# LED_Matrix_MCI_Vorlage.net
KiCad netlist of a schematic drawn in Altium Designer
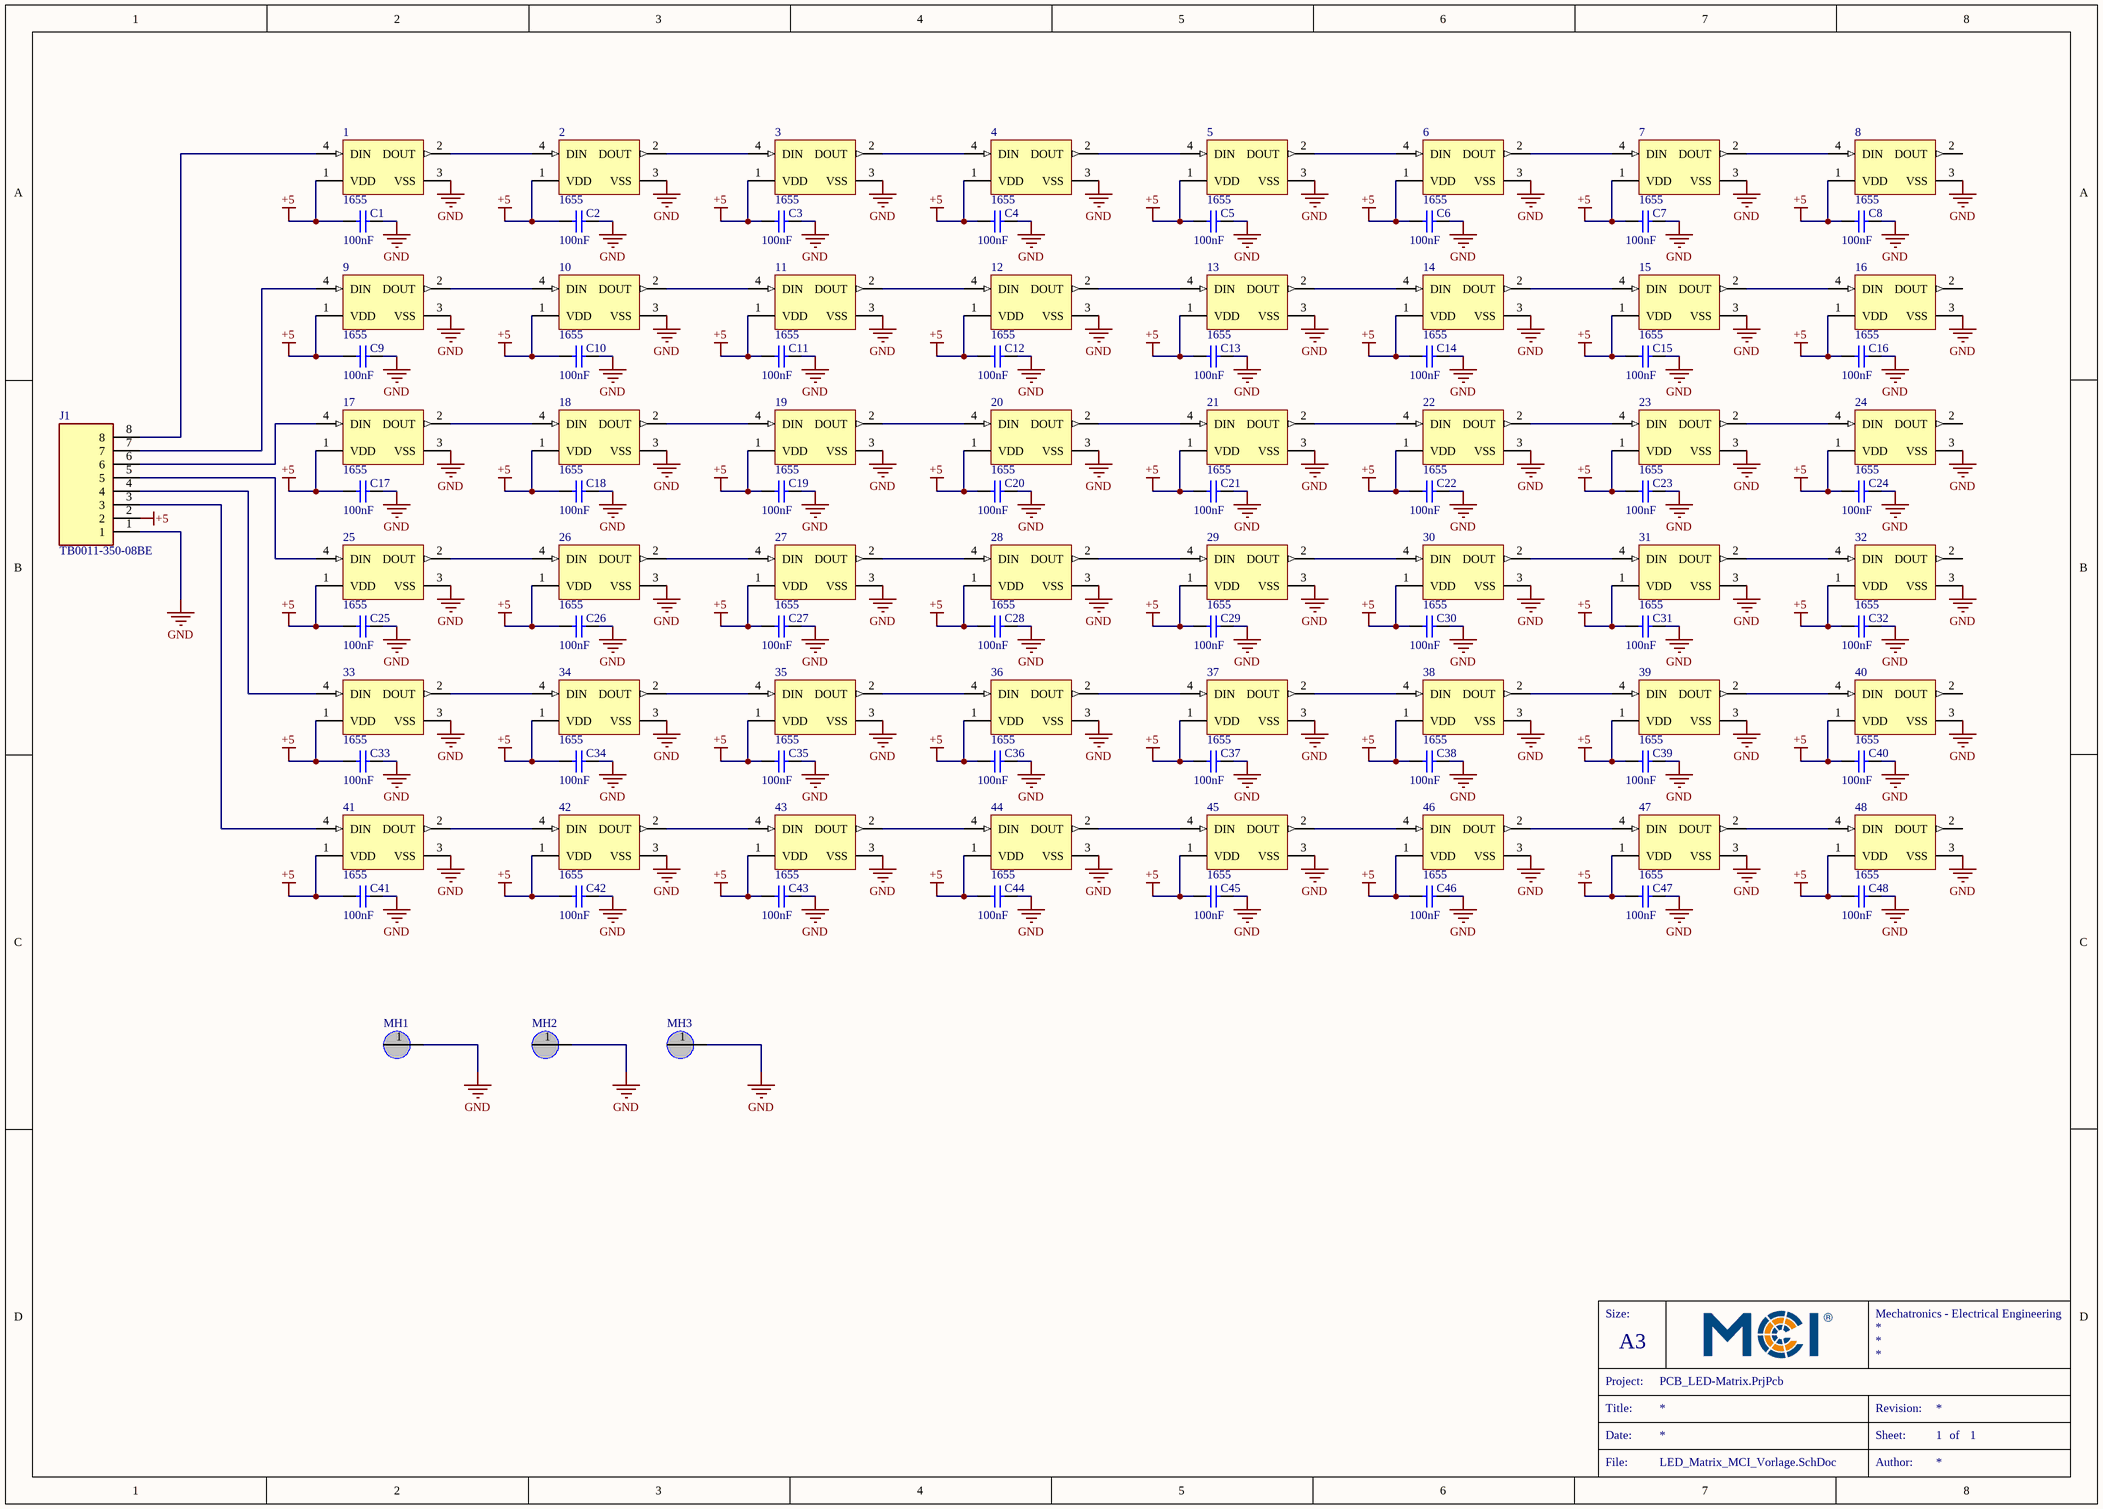
[diagram p0: LED_Matrix_MCI_Vorlage.SchDoc]

(export (version "E")
  (design (tool "Eeschema 10.0.6"))
  (components
    (comp (ref "1")
      (value "1655")
      (footprint "ADA-RGB-1655_V")
      (fields (field (name "MANUFACTURER") "Adafruit-Industries-LLC"))
      (libsource (lib "Altium Content Vault") (part "ADA-RGB-1655-4"))
    )
    (comp (ref "2")
      (value "1655")
      (footprint "ADA-RGB-1655_V")
      (fields (field (name "MANUFACTURER") "Adafruit-Industries-LLC"))
      (libsource (lib "Altium Content Vault") (part "ADA-RGB-1655-4"))
    )
    (comp (ref "3")
      (value "1655")
      (footprint "ADA-RGB-1655_V")
      (fields (field (name "MANUFACTURER") "Adafruit-Industries-LLC"))
      (libsource (lib "Altium Content Vault") (part "ADA-RGB-1655-4"))
    )
    (comp (ref "4")
      (value "1655")
      (footprint "ADA-RGB-1655_V")
      (fields (field (name "MANUFACTURER") "Adafruit-Industries-LLC"))
      (libsource (lib "Altium Content Vault") (part "ADA-RGB-1655-4"))
    )
    (comp (ref "5")
      (value "1655")
      (footprint "ADA-RGB-1655_V")
      (fields (field (name "MANUFACTURER") "Adafruit-Industries-LLC"))
      (libsource (lib "Altium Content Vault") (part "ADA-RGB-1655-4"))
    )
    (comp (ref "6")
      (value "1655")
      (footprint "ADA-RGB-1655_V")
      (fields (field (name "MANUFACTURER") "Adafruit-Industries-LLC"))
      (libsource (lib "Altium Content Vault") (part "ADA-RGB-1655-4"))
    )
    (comp (ref "7")
      (value "1655")
      (footprint "ADA-RGB-1655_V")
      (fields (field (name "MANUFACTURER") "Adafruit-Industries-LLC"))
      (libsource (lib "Altium Content Vault") (part "ADA-RGB-1655-4"))
    )
    (comp (ref "8")
      (value "1655")
      (footprint "ADA-RGB-1655_V")
      (fields (field (name "MANUFACTURER") "Adafruit-Industries-LLC"))
      (libsource (lib "Altium Content Vault") (part "ADA-RGB-1655-4"))
    )
    (comp (ref "9")
      (value "1655")
      (footprint "ADA-RGB-1655_V")
      (fields (field (name "MANUFACTURER") "Adafruit-Industries-LLC"))
      (libsource (lib "Altium Content Vault") (part "ADA-RGB-1655-4"))
    )
    (comp (ref "10")
      (value "1655")
      (footprint "ADA-RGB-1655_V")
      (fields (field (name "MANUFACTURER") "Adafruit-Industries-LLC"))
      (libsource (lib "Altium Content Vault") (part "ADA-RGB-1655-4"))
    )
    (comp (ref "11")
      (value "1655")
      (footprint "ADA-RGB-1655_V")
      (fields (field (name "MANUFACTURER") "Adafruit-Industries-LLC"))
      (libsource (lib "Altium Content Vault") (part "ADA-RGB-1655-4"))
    )
    (comp (ref "12")
      (value "1655")
      (footprint "ADA-RGB-1655_V")
      (fields (field (name "MANUFACTURER") "Adafruit-Industries-LLC"))
      (libsource (lib "Altium Content Vault") (part "ADA-RGB-1655-4"))
    )
    (comp (ref "13")
      (value "1655")
      (footprint "ADA-RGB-1655_V")
      (fields (field (name "MANUFACTURER") "Adafruit-Industries-LLC"))
      (libsource (lib "Altium Content Vault") (part "ADA-RGB-1655-4"))
    )
    (comp (ref "14")
      (value "1655")
      (footprint "ADA-RGB-1655_V")
      (fields (field (name "MANUFACTURER") "Adafruit-Industries-LLC"))
      (libsource (lib "Altium Content Vault") (part "ADA-RGB-1655-4"))
    )
    (comp (ref "15")
      (value "1655")
      (footprint "ADA-RGB-1655_V")
      (fields (field (name "MANUFACTURER") "Adafruit-Industries-LLC"))
      (libsource (lib "Altium Content Vault") (part "ADA-RGB-1655-4"))
    )
    (comp (ref "16")
      (value "1655")
      (footprint "ADA-RGB-1655_V")
      (fields (field (name "MANUFACTURER") "Adafruit-Industries-LLC"))
      (libsource (lib "Altium Content Vault") (part "ADA-RGB-1655-4"))
    )
    (comp (ref "17")
      (value "1655")
      (footprint "ADA-RGB-1655_V")
      (fields (field (name "MANUFACTURER") "Adafruit-Industries-LLC"))
      (libsource (lib "Altium Content Vault") (part "ADA-RGB-1655-4"))
    )
    (comp (ref "18")
      (value "1655")
      (footprint "ADA-RGB-1655_V")
      (fields (field (name "MANUFACTURER") "Adafruit-Industries-LLC"))
      (libsource (lib "Altium Content Vault") (part "ADA-RGB-1655-4"))
    )
    (comp (ref "19")
      (value "1655")
      (footprint "ADA-RGB-1655_V")
      (fields (field (name "MANUFACTURER") "Adafruit-Industries-LLC"))
      (libsource (lib "Altium Content Vault") (part "ADA-RGB-1655-4"))
    )
    (comp (ref "20")
      (value "1655")
      (footprint "ADA-RGB-1655_V")
      (fields (field (name "MANUFACTURER") "Adafruit-Industries-LLC"))
      (libsource (lib "Altium Content Vault") (part "ADA-RGB-1655-4"))
    )
    (comp (ref "21")
      (value "1655")
      (footprint "ADA-RGB-1655_V")
      (fields (field (name "MANUFACTURER") "Adafruit-Industries-LLC"))
      (libsource (lib "Altium Content Vault") (part "ADA-RGB-1655-4"))
    )
    (comp (ref "22")
      (value "1655")
      (footprint "ADA-RGB-1655_V")
      (fields (field (name "MANUFACTURER") "Adafruit-Industries-LLC"))
      (libsource (lib "Altium Content Vault") (part "ADA-RGB-1655-4"))
    )
    (comp (ref "23")
      (value "1655")
      (footprint "ADA-RGB-1655_V")
      (fields (field (name "MANUFACTURER") "Adafruit-Industries-LLC"))
      (libsource (lib "Altium Content Vault") (part "ADA-RGB-1655-4"))
    )
    (comp (ref "24")
      (value "1655")
      (footprint "ADA-RGB-1655_V")
      (fields (field (name "MANUFACTURER") "Adafruit-Industries-LLC"))
      (libsource (lib "Altium Content Vault") (part "ADA-RGB-1655-4"))
    )
    (comp (ref "25")
      (value "1655")
      (footprint "ADA-RGB-1655_V")
      (fields (field (name "MANUFACTURER") "Adafruit-Industries-LLC"))
      (libsource (lib "Altium Content Vault") (part "ADA-RGB-1655-4"))
    )
    (comp (ref "26")
      (value "1655")
      (footprint "ADA-RGB-1655_V")
      (fields (field (name "MANUFACTURER") "Adafruit-Industries-LLC"))
      (libsource (lib "Altium Content Vault") (part "ADA-RGB-1655-4"))
    )
    (comp (ref "27")
      (value "1655")
      (footprint "ADA-RGB-1655_V")
      (fields (field (name "MANUFACTURER") "Adafruit-Industries-LLC"))
      (libsource (lib "Altium Content Vault") (part "ADA-RGB-1655-4"))
    )
    (comp (ref "28")
      (value "1655")
      (footprint "ADA-RGB-1655_V")
      (fields (field (name "MANUFACTURER") "Adafruit-Industries-LLC"))
      (libsource (lib "Altium Content Vault") (part "ADA-RGB-1655-4"))
    )
    (comp (ref "29")
      (value "1655")
      (footprint "ADA-RGB-1655_V")
      (fields (field (name "MANUFACTURER") "Adafruit-Industries-LLC"))
      (libsource (lib "Altium Content Vault") (part "ADA-RGB-1655-4"))
    )
    (comp (ref "30")
      (value "1655")
      (footprint "ADA-RGB-1655_V")
      (fields (field (name "MANUFACTURER") "Adafruit-Industries-LLC"))
      (libsource (lib "Altium Content Vault") (part "ADA-RGB-1655-4"))
    )
    (comp (ref "31")
      (value "1655")
      (footprint "ADA-RGB-1655_V")
      (fields (field (name "MANUFACTURER") "Adafruit-Industries-LLC"))
      (libsource (lib "Altium Content Vault") (part "ADA-RGB-1655-4"))
    )
    (comp (ref "32")
      (value "1655")
      (footprint "ADA-RGB-1655_V")
      (fields (field (name "MANUFACTURER") "Adafruit-Industries-LLC"))
      (libsource (lib "Altium Content Vault") (part "ADA-RGB-1655-4"))
    )
    (comp (ref "33")
      (value "1655")
      (footprint "ADA-RGB-1655_V")
      (fields (field (name "MANUFACTURER") "Adafruit-Industries-LLC"))
      (libsource (lib "Altium Content Vault") (part "ADA-RGB-1655-4"))
    )
    (comp (ref "34")
      (value "1655")
      (footprint "ADA-RGB-1655_V")
      (fields (field (name "MANUFACTURER") "Adafruit-Industries-LLC"))
      (libsource (lib "Altium Content Vault") (part "ADA-RGB-1655-4"))
    )
    (comp (ref "35")
      (value "1655")
      (footprint "ADA-RGB-1655_V")
      (fields (field (name "MANUFACTURER") "Adafruit-Industries-LLC"))
      (libsource (lib "Altium Content Vault") (part "ADA-RGB-1655-4"))
    )
    (comp (ref "36")
      (value "1655")
      (footprint "ADA-RGB-1655_V")
      (fields (field (name "MANUFACTURER") "Adafruit-Industries-LLC"))
      (libsource (lib "Altium Content Vault") (part "ADA-RGB-1655-4"))
    )
    (comp (ref "37")
      (value "1655")
      (footprint "ADA-RGB-1655_V")
      (fields (field (name "MANUFACTURER") "Adafruit-Industries-LLC"))
      (libsource (lib "Altium Content Vault") (part "ADA-RGB-1655-4"))
    )
    (comp (ref "38")
      (value "1655")
      (footprint "ADA-RGB-1655_V")
      (fields (field (name "MANUFACTURER") "Adafruit-Industries-LLC"))
      (libsource (lib "Altium Content Vault") (part "ADA-RGB-1655-4"))
    )
    (comp (ref "39")
      (value "1655")
      (footprint "ADA-RGB-1655_V")
      (fields (field (name "MANUFACTURER") "Adafruit-Industries-LLC"))
      (libsource (lib "Altium Content Vault") (part "ADA-RGB-1655-4"))
    )
    (comp (ref "40")
      (value "1655")
      (footprint "ADA-RGB-1655_V")
      (fields (field (name "MANUFACTURER") "Adafruit-Industries-LLC"))
      (libsource (lib "Altium Content Vault") (part "ADA-RGB-1655-4"))
    )
    (comp (ref "41")
      (value "1655")
      (footprint "ADA-RGB-1655_V")
      (fields (field (name "MANUFACTURER") "Adafruit-Industries-LLC"))
      (libsource (lib "Altium Content Vault") (part "ADA-RGB-1655-4"))
    )
    (comp (ref "42")
      (value "1655")
      (footprint "ADA-RGB-1655_V")
      (fields (field (name "MANUFACTURER") "Adafruit-Industries-LLC"))
      (libsource (lib "Altium Content Vault") (part "ADA-RGB-1655-4"))
    )
    (comp (ref "43")
      (value "1655")
      (footprint "ADA-RGB-1655_V")
      (fields (field (name "MANUFACTURER") "Adafruit-Industries-LLC"))
      (libsource (lib "Altium Content Vault") (part "ADA-RGB-1655-4"))
    )
    (comp (ref "44")
      (value "1655")
      (footprint "ADA-RGB-1655_V")
      (fields (field (name "MANUFACTURER") "Adafruit-Industries-LLC"))
      (libsource (lib "Altium Content Vault") (part "ADA-RGB-1655-4"))
    )
    (comp (ref "45")
      (value "1655")
      (footprint "ADA-RGB-1655_V")
      (fields (field (name "MANUFACTURER") "Adafruit-Industries-LLC"))
      (libsource (lib "Altium Content Vault") (part "ADA-RGB-1655-4"))
    )
    (comp (ref "46")
      (value "1655")
      (footprint "ADA-RGB-1655_V")
      (fields (field (name "MANUFACTURER") "Adafruit-Industries-LLC"))
      (libsource (lib "Altium Content Vault") (part "ADA-RGB-1655-4"))
    )
    (comp (ref "47")
      (value "1655")
      (footprint "ADA-RGB-1655_V")
      (fields (field (name "MANUFACTURER") "Adafruit-Industries-LLC"))
      (libsource (lib "Altium Content Vault") (part "ADA-RGB-1655-4"))
    )
    (comp (ref "48")
      (value "1655")
      (footprint "ADA-RGB-1655_V")
      (fields (field (name "MANUFACTURER") "Adafruit-Industries-LLC"))
      (libsource (lib "Altium Content Vault") (part "ADA-RGB-1655-4"))
    )
    (comp (ref "C1")
      (value "100nF")
      (footprint "CAPC0805(2012)100_M")
      (description "CAP 100nF 10V ±5% 0805 (2012 Metric) Thickness 1mm SMD")
      (fields (field (name "TOLERANCE") "Â±5%"))
      (libsource (lib "Altium Content Vault") (part "CAP"))
    )
    (comp (ref "C2")
      (value "100nF")
      (footprint "CAPC0805(2012)100_M")
      (description "CAP 100nF 10V ±5% 0805 (2012 Metric) Thickness 1mm SMD")
      (fields (field (name "TOLERANCE") "Â±5%"))
      (libsource (lib "Altium Content Vault") (part "CAP"))
    )
    (comp (ref "C3")
      (value "100nF")
      (footprint "CAPC0805(2012)100_M")
      (description "CAP 100nF 10V ±5% 0805 (2012 Metric) Thickness 1mm SMD")
      (fields (field (name "TOLERANCE") "Â±5%"))
      (libsource (lib "Altium Content Vault") (part "CAP"))
    )
    (comp (ref "C4")
      (value "100nF")
      (footprint "CAPC0805(2012)100_M")
      (description "CAP 100nF 10V ±5% 0805 (2012 Metric) Thickness 1mm SMD")
      (fields (field (name "TOLERANCE") "Â±5%"))
      (libsource (lib "Altium Content Vault") (part "CAP"))
    )
    (comp (ref "C5")
      (value "100nF")
      (footprint "CAPC0805(2012)100_M")
      (description "CAP 100nF 10V ±5% 0805 (2012 Metric) Thickness 1mm SMD")
      (fields (field (name "TOLERANCE") "Â±5%"))
      (libsource (lib "Altium Content Vault") (part "CAP"))
    )
    (comp (ref "C6")
      (value "100nF")
      (footprint "CAPC0805(2012)100_M")
      (description "CAP 100nF 10V ±5% 0805 (2012 Metric) Thickness 1mm SMD")
      (fields (field (name "TOLERANCE") "Â±5%"))
      (libsource (lib "Altium Content Vault") (part "CAP"))
    )
    (comp (ref "C7")
      (value "100nF")
      (footprint "CAPC0805(2012)100_M")
      (description "CAP 100nF 10V ±5% 0805 (2012 Metric) Thickness 1mm SMD")
      (fields (field (name "TOLERANCE") "Â±5%"))
      (libsource (lib "Altium Content Vault") (part "CAP"))
    )
    (comp (ref "C8")
      (value "100nF")
      (footprint "CAPC0805(2012)100_M")
      (description "CAP 100nF 10V ±5% 0805 (2012 Metric) Thickness 1mm SMD")
      (fields (field (name "TOLERANCE") "Â±5%"))
      (libsource (lib "Altium Content Vault") (part "CAP"))
    )
    (comp (ref "C9")
      (value "100nF")
      (footprint "CAPC0805(2012)100_M")
      (description "CAP 100nF 10V ±5% 0805 (2012 Metric) Thickness 1mm SMD")
      (fields (field (name "TOLERANCE") "Â±5%"))
      (libsource (lib "Altium Content Vault") (part "CAP"))
    )
    (comp (ref "C10")
      (value "100nF")
      (footprint "CAPC0805(2012)100_M")
      (description "CAP 100nF 10V ±5% 0805 (2012 Metric) Thickness 1mm SMD")
      (fields (field (name "TOLERANCE") "Â±5%"))
      (libsource (lib "Altium Content Vault") (part "CAP"))
    )
    (comp (ref "C11")
      (value "100nF")
      (footprint "CAPC0805(2012)100_M")
      (description "CAP 100nF 10V ±5% 0805 (2012 Metric) Thickness 1mm SMD")
      (fields (field (name "TOLERANCE") "Â±5%"))
      (libsource (lib "Altium Content Vault") (part "CAP"))
    )
    (comp (ref "C12")
      (value "100nF")
      (footprint "CAPC0805(2012)100_M")
      (description "CAP 100nF 10V ±5% 0805 (2012 Metric) Thickness 1mm SMD")
      (fields (field (name "TOLERANCE") "Â±5%"))
      (libsource (lib "Altium Content Vault") (part "CAP"))
    )
    (comp (ref "C13")
      (value "100nF")
      (footprint "CAPC0805(2012)100_M")
      (description "CAP 100nF 10V ±5% 0805 (2012 Metric) Thickness 1mm SMD")
      (fields (field (name "TOLERANCE") "Â±5%"))
      (libsource (lib "Altium Content Vault") (part "CAP"))
    )
    (comp (ref "C14")
      (value "100nF")
      (footprint "CAPC0805(2012)100_M")
      (description "CAP 100nF 10V ±5% 0805 (2012 Metric) Thickness 1mm SMD")
      (fields (field (name "TOLERANCE") "Â±5%"))
      (libsource (lib "Altium Content Vault") (part "CAP"))
    )
    (comp (ref "C15")
      (value "100nF")
      (footprint "CAPC0805(2012)100_M")
      (description "CAP 100nF 10V ±5% 0805 (2012 Metric) Thickness 1mm SMD")
      (fields (field (name "TOLERANCE") "Â±5%"))
      (libsource (lib "Altium Content Vault") (part "CAP"))
    )
    (comp (ref "C16")
      (value "100nF")
      (footprint "CAPC0805(2012)100_M")
      (description "CAP 100nF 10V ±5% 0805 (2012 Metric) Thickness 1mm SMD")
      (fields (field (name "TOLERANCE") "Â±5%"))
      (libsource (lib "Altium Content Vault") (part "CAP"))
    )
    (comp (ref "C17")
      (value "100nF")
      (footprint "CAPC0805(2012)100_M")
      (description "CAP 100nF 10V ±5% 0805 (2012 Metric) Thickness 1mm SMD")
      (fields (field (name "TOLERANCE") "Â±5%"))
      (libsource (lib "Altium Content Vault") (part "CAP"))
    )
    (comp (ref "C18")
      (value "100nF")
      (footprint "CAPC0805(2012)100_M")
      (description "CAP 100nF 10V ±5% 0805 (2012 Metric) Thickness 1mm SMD")
      (fields (field (name "TOLERANCE") "Â±5%"))
      (libsource (lib "Altium Content Vault") (part "CAP"))
    )
    (comp (ref "C19")
      (value "100nF")
      (footprint "CAPC0805(2012)100_M")
      (description "CAP 100nF 10V ±5% 0805 (2012 Metric) Thickness 1mm SMD")
      (fields (field (name "TOLERANCE") "Â±5%"))
      (libsource (lib "Altium Content Vault") (part "CAP"))
    )
    (comp (ref "C20")
      (value "100nF")
      (footprint "CAPC0805(2012)100_M")
      (description "CAP 100nF 10V ±5% 0805 (2012 Metric) Thickness 1mm SMD")
      (fields (field (name "TOLERANCE") "Â±5%"))
      (libsource (lib "Altium Content Vault") (part "CAP"))
    )
    (comp (ref "C21")
      (value "100nF")
      (footprint "CAPC0805(2012)100_M")
      (description "CAP 100nF 10V ±5% 0805 (2012 Metric) Thickness 1mm SMD")
      (fields (field (name "TOLERANCE") "Â±5%"))
      (libsource (lib "Altium Content Vault") (part "CAP"))
    )
    (comp (ref "C22")
      (value "100nF")
      (footprint "CAPC0805(2012)100_M")
      (description "CAP 100nF 10V ±5% 0805 (2012 Metric) Thickness 1mm SMD")
      (fields (field (name "TOLERANCE") "Â±5%"))
      (libsource (lib "Altium Content Vault") (part "CAP"))
    )
    (comp (ref "C23")
      (value "100nF")
      (footprint "CAPC0805(2012)100_M")
      (description "CAP 100nF 10V ±5% 0805 (2012 Metric) Thickness 1mm SMD")
      (fields (field (name "TOLERANCE") "Â±5%"))
      (libsource (lib "Altium Content Vault") (part "CAP"))
    )
    (comp (ref "C24")
      (value "100nF")
      (footprint "CAPC0805(2012)100_M")
      (description "CAP 100nF 10V ±5% 0805 (2012 Metric) Thickness 1mm SMD")
      (fields (field (name "TOLERANCE") "Â±5%"))
      (libsource (lib "Altium Content Vault") (part "CAP"))
    )
    (comp (ref "C25")
      (value "100nF")
      (footprint "CAPC0805(2012)100_M")
      (description "CAP 100nF 10V ±5% 0805 (2012 Metric) Thickness 1mm SMD")
      (fields (field (name "TOLERANCE") "Â±5%"))
      (libsource (lib "Altium Content Vault") (part "CAP"))
    )
    (comp (ref "C26")
      (value "100nF")
      (footprint "CAPC0805(2012)100_M")
      (description "CAP 100nF 10V ±5% 0805 (2012 Metric) Thickness 1mm SMD")
      (fields (field (name "TOLERANCE") "Â±5%"))
      (libsource (lib "Altium Content Vault") (part "CAP"))
    )
    (comp (ref "C27")
      (value "100nF")
      (footprint "CAPC0805(2012)100_M")
      (description "CAP 100nF 10V ±5% 0805 (2012 Metric) Thickness 1mm SMD")
      (fields (field (name "TOLERANCE") "Â±5%"))
      (libsource (lib "Altium Content Vault") (part "CAP"))
    )
    (comp (ref "C28")
      (value "100nF")
      (footprint "CAPC0805(2012)100_M")
      (description "CAP 100nF 10V ±5% 0805 (2012 Metric) Thickness 1mm SMD")
      (fields (field (name "TOLERANCE") "Â±5%"))
      (libsource (lib "Altium Content Vault") (part "CAP"))
    )
    (comp (ref "C29")
      (value "100nF")
      (footprint "CAPC0805(2012)100_M")
      (description "CAP 100nF 10V ±5% 0805 (2012 Metric) Thickness 1mm SMD")
      (fields (field (name "TOLERANCE") "Â±5%"))
      (libsource (lib "Altium Content Vault") (part "CAP"))
    )
    (comp (ref "C30")
      (value "100nF")
      (footprint "CAPC0805(2012)100_M")
      (description "CAP 100nF 10V ±5% 0805 (2012 Metric) Thickness 1mm SMD")
      (fields (field (name "TOLERANCE") "Â±5%"))
      (libsource (lib "Altium Content Vault") (part "CAP"))
    )
    (comp (ref "C31")
      (value "100nF")
      (footprint "CAPC0805(2012)100_M")
      (description "CAP 100nF 10V ±5% 0805 (2012 Metric) Thickness 1mm SMD")
      (fields (field (name "TOLERANCE") "Â±5%"))
      (libsource (lib "Altium Content Vault") (part "CAP"))
    )
    (comp (ref "C32")
      (value "100nF")
      (footprint "CAPC0805(2012)100_M")
      (description "CAP 100nF 10V ±5% 0805 (2012 Metric) Thickness 1mm SMD")
      (fields (field (name "TOLERANCE") "Â±5%"))
      (libsource (lib "Altium Content Vault") (part "CAP"))
    )
    (comp (ref "C33")
      (value "100nF")
      (footprint "CAPC0805(2012)100_M")
      (description "CAP 100nF 10V ±5% 0805 (2012 Metric) Thickness 1mm SMD")
      (fields (field (name "TOLERANCE") "Â±5%"))
      (libsource (lib "Altium Content Vault") (part "CAP"))
    )
    (comp (ref "C34")
      (value "100nF")
      (footprint "CAPC0805(2012)100_M")
      (description "CAP 100nF 10V ±5% 0805 (2012 Metric) Thickness 1mm SMD")
      (fields (field (name "TOLERANCE") "Â±5%"))
      (libsource (lib "Altium Content Vault") (part "CAP"))
    )
    (comp (ref "C35")
      (value "100nF")
      (footprint "CAPC0805(2012)100_M")
      (description "CAP 100nF 10V ±5% 0805 (2012 Metric) Thickness 1mm SMD")
      (fields (field (name "TOLERANCE") "Â±5%"))
      (libsource (lib "Altium Content Vault") (part "CAP"))
    )
    (comp (ref "C36")
      (value "100nF")
      (footprint "CAPC0805(2012)100_M")
      (description "CAP 100nF 10V ±5% 0805 (2012 Metric) Thickness 1mm SMD")
      (fields (field (name "TOLERANCE") "Â±5%"))
      (libsource (lib "Altium Content Vault") (part "CAP"))
    )
    (comp (ref "C37")
      (value "100nF")
      (footprint "CAPC0805(2012)100_M")
      (description "CAP 100nF 10V ±5% 0805 (2012 Metric) Thickness 1mm SMD")
      (fields (field (name "TOLERANCE") "Â±5%"))
      (libsource (lib "Altium Content Vault") (part "CAP"))
    )
    (comp (ref "C38")
      (value "100nF")
      (footprint "CAPC0805(2012)100_M")
      (description "CAP 100nF 10V ±5% 0805 (2012 Metric) Thickness 1mm SMD")
      (fields (field (name "TOLERANCE") "Â±5%"))
      (libsource (lib "Altium Content Vault") (part "CAP"))
    )
    (comp (ref "C39")
      (value "100nF")
      (footprint "CAPC0805(2012)100_M")
      (description "CAP 100nF 10V ±5% 0805 (2012 Metric) Thickness 1mm SMD")
      (fields (field (name "TOLERANCE") "Â±5%"))
      (libsource (lib "Altium Content Vault") (part "CAP"))
    )
    (comp (ref "C40")
      (value "100nF")
      (footprint "CAPC0805(2012)100_M")
      (description "CAP 100nF 10V ±5% 0805 (2012 Metric) Thickness 1mm SMD")
      (fields (field (name "TOLERANCE") "Â±5%"))
      (libsource (lib "Altium Content Vault") (part "CAP"))
    )
    (comp (ref "C41")
      (value "100nF")
      (footprint "CAPC0805(2012)100_M")
      (description "CAP 100nF 10V ±5% 0805 (2012 Metric) Thickness 1mm SMD")
      (fields (field (name "TOLERANCE") "Â±5%"))
      (libsource (lib "Altium Content Vault") (part "CAP"))
    )
    (comp (ref "C42")
      (value "100nF")
      (footprint "CAPC0805(2012)100_M")
      (description "CAP 100nF 10V ±5% 0805 (2012 Metric) Thickness 1mm SMD")
      (fields (field (name "TOLERANCE") "Â±5%"))
      (libsource (lib "Altium Content Vault") (part "CAP"))
    )
    (comp (ref "C43")
      (value "100nF")
      (footprint "CAPC0805(2012)100_M")
      (description "CAP 100nF 10V ±5% 0805 (2012 Metric) Thickness 1mm SMD")
      (fields (field (name "TOLERANCE") "Â±5%"))
      (libsource (lib "Altium Content Vault") (part "CAP"))
    )
    (comp (ref "C44")
      (value "100nF")
      (footprint "CAPC0805(2012)100_M")
      (description "CAP 100nF 10V ±5% 0805 (2012 Metric) Thickness 1mm SMD")
      (fields (field (name "TOLERANCE") "Â±5%"))
      (libsource (lib "Altium Content Vault") (part "CAP"))
    )
    (comp (ref "C45")
      (value "100nF")
      (footprint "CAPC0805(2012)100_M")
      (description "CAP 100nF 10V ±5% 0805 (2012 Metric) Thickness 1mm SMD")
      (fields (field (name "TOLERANCE") "Â±5%"))
      (libsource (lib "Altium Content Vault") (part "CAP"))
    )
    (comp (ref "C46")
      (value "100nF")
      (footprint "CAPC0805(2012)100_M")
      (description "CAP 100nF 10V ±5% 0805 (2012 Metric) Thickness 1mm SMD")
      (fields (field (name "TOLERANCE") "Â±5%"))
      (libsource (lib "Altium Content Vault") (part "CAP"))
    )
    (comp (ref "C47")
      (value "100nF")
      (footprint "CAPC0805(2012)100_M")
      (description "CAP 100nF 10V ±5% 0805 (2012 Metric) Thickness 1mm SMD")
      (fields (field (name "TOLERANCE") "Â±5%"))
      (libsource (lib "Altium Content Vault") (part "CAP"))
    )
    (comp (ref "C48")
      (value "100nF")
      (footprint "CAPC0805(2012)100_M")
      (description "CAP 100nF 10V ±5% 0805 (2012 Metric) Thickness 1mm SMD")
      (fields (field (name "TOLERANCE") "Â±5%"))
      (libsource (lib "Altium Content Vault") (part "CAP"))
    )
    (comp (ref "J1")
      (value "TB0011-350-08BE")
      (footprint "TB0011-350-08BE")
      (description "Connector")
      (libsource (lib "Library") (part "TB0011-350-08BE"))
    )
    (comp (ref "MH1")
      (value "MountingHole")
      (footprint "MTH")
      (libsource (lib "PCB_LED-Matrix") (part "MountingHole"))
    )
    (comp (ref "MH2")
      (value "MountingHole")
      (footprint "MTH")
      (libsource (lib "PCB_LED-Matrix") (part "MountingHole"))
    )
    (comp (ref "MH3")
      (value "MountingHole")
      (footprint "MTH")
      (libsource (lib "PCB_LED-Matrix") (part "MountingHole"))
    )
  )
  (nets
    (net (code "1") (name "+5") (class "Default")
      (node (ref "1") (pin "1") (pinfunction "VDD_1") (pintype "power_in"))
      (node (ref "10") (pin "1") (pinfunction "VDD_1") (pintype "power_in"))
      (node (ref "11") (pin "1") (pinfunction "VDD_1") (pintype "power_in"))
      (node (ref "12") (pin "1") (pinfunction "VDD_1") (pintype "power_in"))
      (node (ref "13") (pin "1") (pinfunction "VDD_1") (pintype "power_in"))
      (node (ref "14") (pin "1") (pinfunction "VDD_1") (pintype "power_in"))
      (node (ref "15") (pin "1") (pinfunction "VDD_1") (pintype "power_in"))
      (node (ref "16") (pin "1") (pinfunction "VDD_1") (pintype "power_in"))
      (node (ref "17") (pin "1") (pinfunction "VDD_1") (pintype "power_in"))
      (node (ref "18") (pin "1") (pinfunction "VDD_1") (pintype "power_in"))
      (node (ref "19") (pin "1") (pinfunction "VDD_1") (pintype "power_in"))
      (node (ref "2") (pin "1") (pinfunction "VDD_1") (pintype "power_in"))
      (node (ref "20") (pin "1") (pinfunction "VDD_1") (pintype "power_in"))
      (node (ref "21") (pin "1") (pinfunction "VDD_1") (pintype "power_in"))
      (node (ref "22") (pin "1") (pinfunction "VDD_1") (pintype "power_in"))
      (node (ref "23") (pin "1") (pinfunction "VDD_1") (pintype "power_in"))
      (node (ref "24") (pin "1") (pinfunction "VDD_1") (pintype "power_in"))
      (node (ref "25") (pin "1") (pinfunction "VDD_1") (pintype "power_in"))
      (node (ref "26") (pin "1") (pinfunction "VDD_1") (pintype "power_in"))
      (node (ref "27") (pin "1") (pinfunction "VDD_1") (pintype "power_in"))
      (node (ref "28") (pin "1") (pinfunction "VDD_1") (pintype "power_in"))
      (node (ref "29") (pin "1") (pinfunction "VDD_1") (pintype "power_in"))
      (node (ref "3") (pin "1") (pinfunction "VDD_1") (pintype "power_in"))
      (node (ref "30") (pin "1") (pinfunction "VDD_1") (pintype "power_in"))
      (node (ref "31") (pin "1") (pinfunction "VDD_1") (pintype "power_in"))
      (node (ref "32") (pin "1") (pinfunction "VDD_1") (pintype "power_in"))
      (node (ref "33") (pin "1") (pinfunction "VDD_1") (pintype "power_in"))
      (node (ref "34") (pin "1") (pinfunction "VDD_1") (pintype "power_in"))
      (node (ref "35") (pin "1") (pinfunction "VDD_1") (pintype "power_in"))
      (node (ref "36") (pin "1") (pinfunction "VDD_1") (pintype "power_in"))
      (node (ref "37") (pin "1") (pinfunction "VDD_1") (pintype "power_in"))
      (node (ref "38") (pin "1") (pinfunction "VDD_1") (pintype "power_in"))
      (node (ref "39") (pin "1") (pinfunction "VDD_1") (pintype "power_in"))
      (node (ref "4") (pin "1") (pinfunction "VDD_1") (pintype "power_in"))
      (node (ref "40") (pin "1") (pinfunction "VDD_1") (pintype "power_in"))
      (node (ref "41") (pin "1") (pinfunction "VDD_1") (pintype "power_in"))
      (node (ref "42") (pin "1") (pinfunction "VDD_1") (pintype "power_in"))
      (node (ref "43") (pin "1") (pinfunction "VDD_1") (pintype "power_in"))
      (node (ref "44") (pin "1") (pinfunction "VDD_1") (pintype "power_in"))
      (node (ref "45") (pin "1") (pinfunction "VDD_1") (pintype "power_in"))
      (node (ref "46") (pin "1") (pinfunction "VDD_1") (pintype "power_in"))
      (node (ref "47") (pin "1") (pinfunction "VDD_1") (pintype "power_in"))
      (node (ref "48") (pin "1") (pinfunction "VDD_1") (pintype "power_in"))
      (node (ref "5") (pin "1") (pinfunction "VDD_1") (pintype "power_in"))
      (node (ref "6") (pin "1") (pinfunction "VDD_1") (pintype "power_in"))
      (node (ref "7") (pin "1") (pinfunction "VDD_1") (pintype "power_in"))
      (node (ref "8") (pin "1") (pinfunction "VDD_1") (pintype "power_in"))
      (node (ref "9") (pin "1") (pinfunction "VDD_1") (pintype "power_in"))
      (node (ref "C1") (pin "1") (pinfunction "1_1") (pintype "passive"))
      (node (ref "C10") (pin "1") (pinfunction "1_1") (pintype "passive"))
      (node (ref "C11") (pin "1") (pinfunction "1_1") (pintype "passive"))
      (node (ref "C12") (pin "1") (pinfunction "1_1") (pintype "passive"))
      (node (ref "C13") (pin "1") (pinfunction "1_1") (pintype "passive"))
      (node (ref "C14") (pin "1") (pinfunction "1_1") (pintype "passive"))
      (node (ref "C15") (pin "1") (pinfunction "1_1") (pintype "passive"))
      (node (ref "C16") (pin "1") (pinfunction "1_1") (pintype "passive"))
      (node (ref "C17") (pin "1") (pinfunction "1_1") (pintype "passive"))
      (node (ref "C18") (pin "1") (pinfunction "1_1") (pintype "passive"))
      (node (ref "C19") (pin "1") (pinfunction "1_1") (pintype "passive"))
      (node (ref "C2") (pin "1") (pinfunction "1_1") (pintype "passive"))
      (node (ref "C20") (pin "1") (pinfunction "1_1") (pintype "passive"))
      (node (ref "C21") (pin "1") (pinfunction "1_1") (pintype "passive"))
      (node (ref "C22") (pin "1") (pinfunction "1_1") (pintype "passive"))
      (node (ref "C23") (pin "1") (pinfunction "1_1") (pintype "passive"))
      (node (ref "C24") (pin "1") (pinfunction "1_1") (pintype "passive"))
      (node (ref "C25") (pin "1") (pinfunction "1_1") (pintype "passive"))
      (node (ref "C26") (pin "1") (pinfunction "1_1") (pintype "passive"))
      (node (ref "C27") (pin "1") (pinfunction "1_1") (pintype "passive"))
      (node (ref "C28") (pin "1") (pinfunction "1_1") (pintype "passive"))
      (node (ref "C29") (pin "1") (pinfunction "1_1") (pintype "passive"))
      (node (ref "C3") (pin "1") (pinfunction "1_1") (pintype "passive"))
      (node (ref "C30") (pin "1") (pinfunction "1_1") (pintype "passive"))
      (node (ref "C31") (pin "1") (pinfunction "1_1") (pintype "passive"))
      (node (ref "C32") (pin "1") (pinfunction "1_1") (pintype "passive"))
      (node (ref "C33") (pin "1") (pinfunction "1_1") (pintype "passive"))
      (node (ref "C34") (pin "1") (pinfunction "1_1") (pintype "passive"))
      (node (ref "C35") (pin "1") (pinfunction "1_1") (pintype "passive"))
      (node (ref "C36") (pin "1") (pinfunction "1_1") (pintype "passive"))
      (node (ref "C37") (pin "1") (pinfunction "1_1") (pintype "passive"))
      (node (ref "C38") (pin "1") (pinfunction "1_1") (pintype "passive"))
      (node (ref "C39") (pin "1") (pinfunction "1_1") (pintype "passive"))
      (node (ref "C4") (pin "1") (pinfunction "1_1") (pintype "passive"))
      (node (ref "C40") (pin "1") (pinfunction "1_1") (pintype "passive"))
      (node (ref "C41") (pin "1") (pinfunction "1_1") (pintype "passive"))
      (node (ref "C42") (pin "1") (pinfunction "1_1") (pintype "passive"))
      (node (ref "C43") (pin "1") (pinfunction "1_1") (pintype "passive"))
      (node (ref "C44") (pin "1") (pinfunction "1_1") (pintype "passive"))
      (node (ref "C45") (pin "1") (pinfunction "1_1") (pintype "passive"))
      (node (ref "C46") (pin "1") (pinfunction "1_1") (pintype "passive"))
      (node (ref "C47") (pin "1") (pinfunction "1_1") (pintype "passive"))
      (node (ref "C48") (pin "1") (pinfunction "1_1") (pintype "passive"))
      (node (ref "C5") (pin "1") (pinfunction "1_1") (pintype "passive"))
      (node (ref "C6") (pin "1") (pinfunction "1_1") (pintype "passive"))
      (node (ref "C7") (pin "1") (pinfunction "1_1") (pintype "passive"))
      (node (ref "C8") (pin "1") (pinfunction "1_1") (pintype "passive"))
      (node (ref "C9") (pin "1") (pinfunction "1_1") (pintype "passive"))
      (node (ref "J1") (pin "2") (pinfunction "2_2") (pintype "passive"))
    )
    (net (code "2") (name "GND") (class "Default")
      (node (ref "1") (pin "3") (pinfunction "VSS_3") (pintype "power_in"))
      (node (ref "10") (pin "3") (pinfunction "VSS_3") (pintype "power_in"))
      (node (ref "11") (pin "3") (pinfunction "VSS_3") (pintype "power_in"))
      (node (ref "12") (pin "3") (pinfunction "VSS_3") (pintype "power_in"))
      (node (ref "13") (pin "3") (pinfunction "VSS_3") (pintype "power_in"))
      (node (ref "14") (pin "3") (pinfunction "VSS_3") (pintype "power_in"))
      (node (ref "15") (pin "3") (pinfunction "VSS_3") (pintype "power_in"))
      (node (ref "16") (pin "3") (pinfunction "VSS_3") (pintype "power_in"))
      (node (ref "17") (pin "3") (pinfunction "VSS_3") (pintype "power_in"))
      (node (ref "18") (pin "3") (pinfunction "VSS_3") (pintype "power_in"))
      (node (ref "19") (pin "3") (pinfunction "VSS_3") (pintype "power_in"))
      (node (ref "2") (pin "3") (pinfunction "VSS_3") (pintype "power_in"))
      (node (ref "20") (pin "3") (pinfunction "VSS_3") (pintype "power_in"))
      (node (ref "21") (pin "3") (pinfunction "VSS_3") (pintype "power_in"))
      (node (ref "22") (pin "3") (pinfunction "VSS_3") (pintype "power_in"))
      (node (ref "23") (pin "3") (pinfunction "VSS_3") (pintype "power_in"))
      (node (ref "24") (pin "3") (pinfunction "VSS_3") (pintype "power_in"))
      (node (ref "25") (pin "3") (pinfunction "VSS_3") (pintype "power_in"))
      (node (ref "26") (pin "3") (pinfunction "VSS_3") (pintype "power_in"))
      (node (ref "27") (pin "3") (pinfunction "VSS_3") (pintype "power_in"))
      (node (ref "28") (pin "3") (pinfunction "VSS_3") (pintype "power_in"))
      (node (ref "29") (pin "3") (pinfunction "VSS_3") (pintype "power_in"))
      (node (ref "3") (pin "3") (pinfunction "VSS_3") (pintype "power_in"))
      (node (ref "30") (pin "3") (pinfunction "VSS_3") (pintype "power_in"))
      (node (ref "31") (pin "3") (pinfunction "VSS_3") (pintype "power_in"))
      (node (ref "32") (pin "3") (pinfunction "VSS_3") (pintype "power_in"))
      (node (ref "33") (pin "3") (pinfunction "VSS_3") (pintype "power_in"))
      (node (ref "34") (pin "3") (pinfunction "VSS_3") (pintype "power_in"))
      (node (ref "35") (pin "3") (pinfunction "VSS_3") (pintype "power_in"))
      (node (ref "36") (pin "3") (pinfunction "VSS_3") (pintype "power_in"))
      (node (ref "37") (pin "3") (pinfunction "VSS_3") (pintype "power_in"))
      (node (ref "38") (pin "3") (pinfunction "VSS_3") (pintype "power_in"))
      (node (ref "39") (pin "3") (pinfunction "VSS_3") (pintype "power_in"))
      (node (ref "4") (pin "3") (pinfunction "VSS_3") (pintype "power_in"))
      (node (ref "40") (pin "3") (pinfunction "VSS_3") (pintype "power_in"))
      (node (ref "41") (pin "3") (pinfunction "VSS_3") (pintype "power_in"))
      (node (ref "42") (pin "3") (pinfunction "VSS_3") (pintype "power_in"))
      (node (ref "43") (pin "3") (pinfunction "VSS_3") (pintype "power_in"))
      (node (ref "44") (pin "3") (pinfunction "VSS_3") (pintype "power_in"))
      (node (ref "45") (pin "3") (pinfunction "VSS_3") (pintype "power_in"))
      (node (ref "46") (pin "3") (pinfunction "VSS_3") (pintype "power_in"))
      (node (ref "47") (pin "3") (pinfunction "VSS_3") (pintype "power_in"))
      (node (ref "48") (pin "3") (pinfunction "VSS_3") (pintype "power_in"))
      (node (ref "5") (pin "3") (pinfunction "VSS_3") (pintype "power_in"))
      (node (ref "6") (pin "3") (pinfunction "VSS_3") (pintype "power_in"))
      (node (ref "7") (pin "3") (pinfunction "VSS_3") (pintype "power_in"))
      (node (ref "8") (pin "3") (pinfunction "VSS_3") (pintype "power_in"))
      (node (ref "9") (pin "3") (pinfunction "VSS_3") (pintype "power_in"))
      (node (ref "C1") (pin "2") (pinfunction "2_2") (pintype "passive"))
      (node (ref "C10") (pin "2") (pinfunction "2_2") (pintype "passive"))
      (node (ref "C11") (pin "2") (pinfunction "2_2") (pintype "passive"))
      (node (ref "C12") (pin "2") (pinfunction "2_2") (pintype "passive"))
      (node (ref "C13") (pin "2") (pinfunction "2_2") (pintype "passive"))
      (node (ref "C14") (pin "2") (pinfunction "2_2") (pintype "passive"))
      (node (ref "C15") (pin "2") (pinfunction "2_2") (pintype "passive"))
      (node (ref "C16") (pin "2") (pinfunction "2_2") (pintype "passive"))
      (node (ref "C17") (pin "2") (pinfunction "2_2") (pintype "passive"))
      (node (ref "C18") (pin "2") (pinfunction "2_2") (pintype "passive"))
      (node (ref "C19") (pin "2") (pinfunction "2_2") (pintype "passive"))
      (node (ref "C2") (pin "2") (pinfunction "2_2") (pintype "passive"))
      (node (ref "C20") (pin "2") (pinfunction "2_2") (pintype "passive"))
      (node (ref "C21") (pin "2") (pinfunction "2_2") (pintype "passive"))
      (node (ref "C22") (pin "2") (pinfunction "2_2") (pintype "passive"))
      (node (ref "C23") (pin "2") (pinfunction "2_2") (pintype "passive"))
      (node (ref "C24") (pin "2") (pinfunction "2_2") (pintype "passive"))
      (node (ref "C25") (pin "2") (pinfunction "2_2") (pintype "passive"))
      (node (ref "C26") (pin "2") (pinfunction "2_2") (pintype "passive"))
      (node (ref "C27") (pin "2") (pinfunction "2_2") (pintype "passive"))
      (node (ref "C28") (pin "2") (pinfunction "2_2") (pintype "passive"))
      (node (ref "C29") (pin "2") (pinfunction "2_2") (pintype "passive"))
      (node (ref "C3") (pin "2") (pinfunction "2_2") (pintype "passive"))
      (node (ref "C30") (pin "2") (pinfunction "2_2") (pintype "passive"))
      (node (ref "C31") (pin "2") (pinfunction "2_2") (pintype "passive"))
      (node (ref "C32") (pin "2") (pinfunction "2_2") (pintype "passive"))
      (node (ref "C33") (pin "2") (pinfunction "2_2") (pintype "passive"))
      (node (ref "C34") (pin "2") (pinfunction "2_2") (pintype "passive"))
      (node (ref "C35") (pin "2") (pinfunction "2_2") (pintype "passive"))
      (node (ref "C36") (pin "2") (pinfunction "2_2") (pintype "passive"))
      (node (ref "C37") (pin "2") (pinfunction "2_2") (pintype "passive"))
      (node (ref "C38") (pin "2") (pinfunction "2_2") (pintype "passive"))
      (node (ref "C39") (pin "2") (pinfunction "2_2") (pintype "passive"))
      (node (ref "C4") (pin "2") (pinfunction "2_2") (pintype "passive"))
      (node (ref "C40") (pin "2") (pinfunction "2_2") (pintype "passive"))
      (node (ref "C41") (pin "2") (pinfunction "2_2") (pintype "passive"))
      (node (ref "C42") (pin "2") (pinfunction "2_2") (pintype "passive"))
      (node (ref "C43") (pin "2") (pinfunction "2_2") (pintype "passive"))
      (node (ref "C44") (pin "2") (pinfunction "2_2") (pintype "passive"))
      (node (ref "C45") (pin "2") (pinfunction "2_2") (pintype "passive"))
      (node (ref "C46") (pin "2") (pinfunction "2_2") (pintype "passive"))
      (node (ref "C47") (pin "2") (pinfunction "2_2") (pintype "passive"))
      (node (ref "C48") (pin "2") (pinfunction "2_2") (pintype "passive"))
      (node (ref "C5") (pin "2") (pinfunction "2_2") (pintype "passive"))
      (node (ref "C6") (pin "2") (pinfunction "2_2") (pintype "passive"))
      (node (ref "C7") (pin "2") (pinfunction "2_2") (pintype "passive"))
      (node (ref "C8") (pin "2") (pinfunction "2_2") (pintype "passive"))
      (node (ref "C9") (pin "2") (pinfunction "2_2") (pintype "passive"))
      (node (ref "J1") (pin "1") (pinfunction "1_1") (pintype "passive"))
      (node (ref "MH1") (pin "1") (pintype "passive"))
      (node (ref "MH2") (pin "1") (pintype "passive"))
      (node (ref "MH3") (pin "1") (pintype "passive"))
    )
    (net (code "3") (name "Net-(1-DIN)") (class "Default")
      (node (ref "1") (pin "4") (pinfunction "DIN_4") (pintype "input"))
      (node (ref "J1") (pin "8") (pinfunction "8_8") (pintype "passive"))
    )
    (net (code "4") (name "Net-(1-DOUT)") (class "Default")
      (node (ref "1") (pin "2") (pinfunction "DOUT_2") (pintype "output"))
      (node (ref "2") (pin "4") (pinfunction "DIN_4") (pintype "input"))
    )
    (net (code "5") (name "Net-(2-DOUT)") (class "Default")
      (node (ref "2") (pin "2") (pinfunction "DOUT_2") (pintype "output"))
      (node (ref "3") (pin "4") (pinfunction "DIN_4") (pintype "input"))
    )
    (net (code "6") (name "Net-(3-DOUT)") (class "Default")
      (node (ref "3") (pin "2") (pinfunction "DOUT_2") (pintype "output"))
      (node (ref "4") (pin "4") (pinfunction "DIN_4") (pintype "input"))
    )
    (net (code "7") (name "Net-(4-DOUT)") (class "Default")
      (node (ref "4") (pin "2") (pinfunction "DOUT_2") (pintype "output"))
      (node (ref "5") (pin "4") (pinfunction "DIN_4") (pintype "input"))
    )
    (net (code "8") (name "Net-(5-DOUT)") (class "Default")
      (node (ref "5") (pin "2") (pinfunction "DOUT_2") (pintype "output"))
      (node (ref "6") (pin "4") (pinfunction "DIN_4") (pintype "input"))
    )
    (net (code "9") (name "Net-(6-DOUT)") (class "Default")
      (node (ref "6") (pin "2") (pinfunction "DOUT_2") (pintype "output"))
      (node (ref "7") (pin "4") (pinfunction "DIN_4") (pintype "input"))
    )
    (net (code "10") (name "Net-(7-DOUT)") (class "Default")
      (node (ref "7") (pin "2") (pinfunction "DOUT_2") (pintype "output"))
      (node (ref "8") (pin "4") (pinfunction "DIN_4") (pintype "input"))
    )
    (net (code "11") (name "Net-(9-DIN)") (class "Default")
      (node (ref "9") (pin "4") (pinfunction "DIN_4") (pintype "input"))
      (node (ref "J1") (pin "7") (pinfunction "7_7") (pintype "passive"))
    )
    (net (code "12") (name "Net-(10-DIN)") (class "Default")
      (node (ref "10") (pin "4") (pinfunction "DIN_4") (pintype "input"))
      (node (ref "9") (pin "2") (pinfunction "DOUT_2") (pintype "output"))
    )
    (net (code "13") (name "Net-(10-DOUT)") (class "Default")
      (node (ref "10") (pin "2") (pinfunction "DOUT_2") (pintype "output"))
      (node (ref "11") (pin "4") (pinfunction "DIN_4") (pintype "input"))
    )
    (net (code "14") (name "Net-(11-DOUT)") (class "Default")
      (node (ref "11") (pin "2") (pinfunction "DOUT_2") (pintype "output"))
      (node (ref "12") (pin "4") (pinfunction "DIN_4") (pintype "input"))
    )
    (net (code "15") (name "Net-(12-DOUT)") (class "Default")
      (node (ref "12") (pin "2") (pinfunction "DOUT_2") (pintype "output"))
      (node (ref "13") (pin "4") (pinfunction "DIN_4") (pintype "input"))
    )
    (net (code "16") (name "Net-(13-DOUT)") (class "Default")
      (node (ref "13") (pin "2") (pinfunction "DOUT_2") (pintype "output"))
      (node (ref "14") (pin "4") (pinfunction "DIN_4") (pintype "input"))
    )
    (net (code "17") (name "Net-(14-DOUT)") (class "Default")
      (node (ref "14") (pin "2") (pinfunction "DOUT_2") (pintype "output"))
      (node (ref "15") (pin "4") (pinfunction "DIN_4") (pintype "input"))
    )
    (net (code "18") (name "Net-(15-DOUT)") (class "Default")
      (node (ref "15") (pin "2") (pinfunction "DOUT_2") (pintype "output"))
      (node (ref "16") (pin "4") (pinfunction "DIN_4") (pintype "input"))
    )
    (net (code "19") (name "Net-(17-DIN)") (class "Default")
      (node (ref "17") (pin "4") (pinfunction "DIN_4") (pintype "input"))
      (node (ref "J1") (pin "6") (pinfunction "6_6") (pintype "passive"))
    )
    (net (code "20") (name "Net-(17-DOUT)") (class "Default")
      (node (ref "17") (pin "2") (pinfunction "DOUT_2") (pintype "output"))
      (node (ref "18") (pin "4") (pinfunction "DIN_4") (pintype "input"))
    )
    (net (code "21") (name "Net-(18-DOUT)") (class "Default")
      (node (ref "18") (pin "2") (pinfunction "DOUT_2") (pintype "output"))
      (node (ref "19") (pin "4") (pinfunction "DIN_4") (pintype "input"))
    )
    (net (code "22") (name "Net-(19-DOUT)") (class "Default")
      (node (ref "19") (pin "2") (pinfunction "DOUT_2") (pintype "output"))
      (node (ref "20") (pin "4") (pinfunction "DIN_4") (pintype "input"))
    )
    (net (code "23") (name "Net-(20-DOUT)") (class "Default")
      (node (ref "20") (pin "2") (pinfunction "DOUT_2") (pintype "output"))
      (node (ref "21") (pin "4") (pinfunction "DIN_4") (pintype "input"))
    )
    (net (code "24") (name "Net-(21-DOUT)") (class "Default")
      (node (ref "21") (pin "2") (pinfunction "DOUT_2") (pintype "output"))
      (node (ref "22") (pin "4") (pinfunction "DIN_4") (pintype "input"))
    )
    (net (code "25") (name "Net-(22-DOUT)") (class "Default")
      (node (ref "22") (pin "2") (pinfunction "DOUT_2") (pintype "output"))
      (node (ref "23") (pin "4") (pinfunction "DIN_4") (pintype "input"))
    )
    (net (code "26") (name "Net-(23-DOUT)") (class "Default")
      (node (ref "23") (pin "2") (pinfunction "DOUT_2") (pintype "output"))
      (node (ref "24") (pin "4") (pinfunction "DIN_4") (pintype "input"))
    )
    (net (code "27") (name "Net-(25-DIN)") (class "Default")
      (node (ref "25") (pin "4") (pinfunction "DIN_4") (pintype "input"))
      (node (ref "J1") (pin "5") (pinfunction "5_5") (pintype "passive"))
    )
    (net (code "28") (name "Net-(25-DOUT)") (class "Default")
      (node (ref "25") (pin "2") (pinfunction "DOUT_2") (pintype "output"))
      (node (ref "26") (pin "4") (pinfunction "DIN_4") (pintype "input"))
    )
    (net (code "29") (name "Net-(26-DOUT)") (class "Default")
      (node (ref "26") (pin "2") (pinfunction "DOUT_2") (pintype "output"))
      (node (ref "27") (pin "4") (pinfunction "DIN_4") (pintype "input"))
    )
    (net (code "30") (name "Net-(27-DOUT)") (class "Default")
      (node (ref "27") (pin "2") (pinfunction "DOUT_2") (pintype "output"))
      (node (ref "28") (pin "4") (pinfunction "DIN_4") (pintype "input"))
    )
    (net (code "31") (name "Net-(28-DOUT)") (class "Default")
      (node (ref "28") (pin "2") (pinfunction "DOUT_2") (pintype "output"))
      (node (ref "29") (pin "4") (pinfunction "DIN_4") (pintype "input"))
    )
    (net (code "32") (name "Net-(29-DOUT)") (class "Default")
      (node (ref "29") (pin "2") (pinfunction "DOUT_2") (pintype "output"))
      (node (ref "30") (pin "4") (pinfunction "DIN_4") (pintype "input"))
    )
    (net (code "33") (name "Net-(30-DOUT)") (class "Default")
      (node (ref "30") (pin "2") (pinfunction "DOUT_2") (pintype "output"))
      (node (ref "31") (pin "4") (pinfunction "DIN_4") (pintype "input"))
    )
    (net (code "34") (name "Net-(31-DOUT)") (class "Default")
      (node (ref "31") (pin "2") (pinfunction "DOUT_2") (pintype "output"))
      (node (ref "32") (pin "4") (pinfunction "DIN_4") (pintype "input"))
    )
    (net (code "35") (name "Net-(33-DIN)") (class "Default")
      (node (ref "33") (pin "4") (pinfunction "DIN_4") (pintype "input"))
      (node (ref "J1") (pin "4") (pinfunction "4_4") (pintype "passive"))
    )
    (net (code "36") (name "Net-(33-DOUT)") (class "Default")
      (node (ref "33") (pin "2") (pinfunction "DOUT_2") (pintype "output"))
      (node (ref "34") (pin "4") (pinfunction "DIN_4") (pintype "input"))
    )
    (net (code "37") (name "Net-(34-DOUT)") (class "Default")
      (node (ref "34") (pin "2") (pinfunction "DOUT_2") (pintype "output"))
      (node (ref "35") (pin "4") (pinfunction "DIN_4") (pintype "input"))
    )
    (net (code "38") (name "Net-(35-DOUT)") (class "Default")
      (node (ref "35") (pin "2") (pinfunction "DOUT_2") (pintype "output"))
      (node (ref "36") (pin "4") (pinfunction "DIN_4") (pintype "input"))
    )
    (net (code "39") (name "Net-(36-DOUT)") (class "Default")
      (node (ref "36") (pin "2") (pinfunction "DOUT_2") (pintype "output"))
      (node (ref "37") (pin "4") (pinfunction "DIN_4") (pintype "input"))
    )
    (net (code "40") (name "Net-(37-DOUT)") (class "Default")
      (node (ref "37") (pin "2") (pinfunction "DOUT_2") (pintype "output"))
      (node (ref "38") (pin "4") (pinfunction "DIN_4") (pintype "input"))
    )
    (net (code "41") (name "Net-(38-DOUT)") (class "Default")
      (node (ref "38") (pin "2") (pinfunction "DOUT_2") (pintype "output"))
      (node (ref "39") (pin "4") (pinfunction "DIN_4") (pintype "input"))
    )
    (net (code "42") (name "Net-(39-DOUT)") (class "Default")
      (node (ref "39") (pin "2") (pinfunction "DOUT_2") (pintype "output"))
      (node (ref "40") (pin "4") (pinfunction "DIN_4") (pintype "input"))
    )
    (net (code "43") (name "Net-(41-DIN)") (class "Default")
      (node (ref "41") (pin "4") (pinfunction "DIN_4") (pintype "input"))
      (node (ref "J1") (pin "3") (pinfunction "3_3") (pintype "passive"))
    )
    (net (code "44") (name "Net-(41-DOUT)") (class "Default")
      (node (ref "41") (pin "2") (pinfunction "DOUT_2") (pintype "output"))
      (node (ref "42") (pin "4") (pinfunction "DIN_4") (pintype "input"))
    )
    (net (code "45") (name "Net-(42-DOUT)") (class "Default")
      (node (ref "42") (pin "2") (pinfunction "DOUT_2") (pintype "output"))
      (node (ref "43") (pin "4") (pinfunction "DIN_4") (pintype "input"))
    )
    (net (code "46") (name "Net-(43-DOUT)") (class "Default")
      (node (ref "43") (pin "2") (pinfunction "DOUT_2") (pintype "output"))
      (node (ref "44") (pin "4") (pinfunction "DIN_4") (pintype "input"))
    )
    (net (code "47") (name "Net-(44-DOUT)") (class "Default")
      (node (ref "44") (pin "2") (pinfunction "DOUT_2") (pintype "output"))
      (node (ref "45") (pin "4") (pinfunction "DIN_4") (pintype "input"))
    )
    (net (code "48") (name "Net-(45-DOUT)") (class "Default")
      (node (ref "45") (pin "2") (pinfunction "DOUT_2") (pintype "output"))
      (node (ref "46") (pin "4") (pinfunction "DIN_4") (pintype "input"))
    )
    (net (code "49") (name "Net-(46-DOUT)") (class "Default")
      (node (ref "46") (pin "2") (pinfunction "DOUT_2") (pintype "output"))
      (node (ref "47") (pin "4") (pinfunction "DIN_4") (pintype "input"))
    )
    (net (code "50") (name "Net-(47-DOUT)") (class "Default")
      (node (ref "47") (pin "2") (pinfunction "DOUT_2") (pintype "output"))
      (node (ref "48") (pin "4") (pinfunction "DIN_4") (pintype "input"))
    )
    (net (code "51") (name "unconnected-(8-DOUT-Pad2)") (class "Default")
      (node (ref "8") (pin "2") (pinfunction "DOUT_2") (pintype "output"))
    )
    (net (code "52") (name "unconnected-(16-DOUT-Pad2)") (class "Default")
      (node (ref "16") (pin "2") (pinfunction "DOUT_2") (pintype "output"))
    )
    (net (code "53") (name "unconnected-(24-DOUT-Pad2)") (class "Default")
      (node (ref "24") (pin "2") (pinfunction "DOUT_2") (pintype "output"))
    )
    (net (code "54") (name "unconnected-(32-DOUT-Pad2)") (class "Default")
      (node (ref "32") (pin "2") (pinfunction "DOUT_2") (pintype "output"))
    )
    (net (code "55") (name "unconnected-(40-DOUT-Pad2)") (class "Default")
      (node (ref "40") (pin "2") (pinfunction "DOUT_2") (pintype "output"))
    )
    (net (code "56") (name "unconnected-(48-DOUT-Pad2)") (class "Default")
      (node (ref "48") (pin "2") (pinfunction "DOUT_2") (pintype "output"))
    )
  )
)
